# SCH_Survival-PC-3000_2026-08-28.net
KiCad netlist of a schematic drawn in EasyEDA
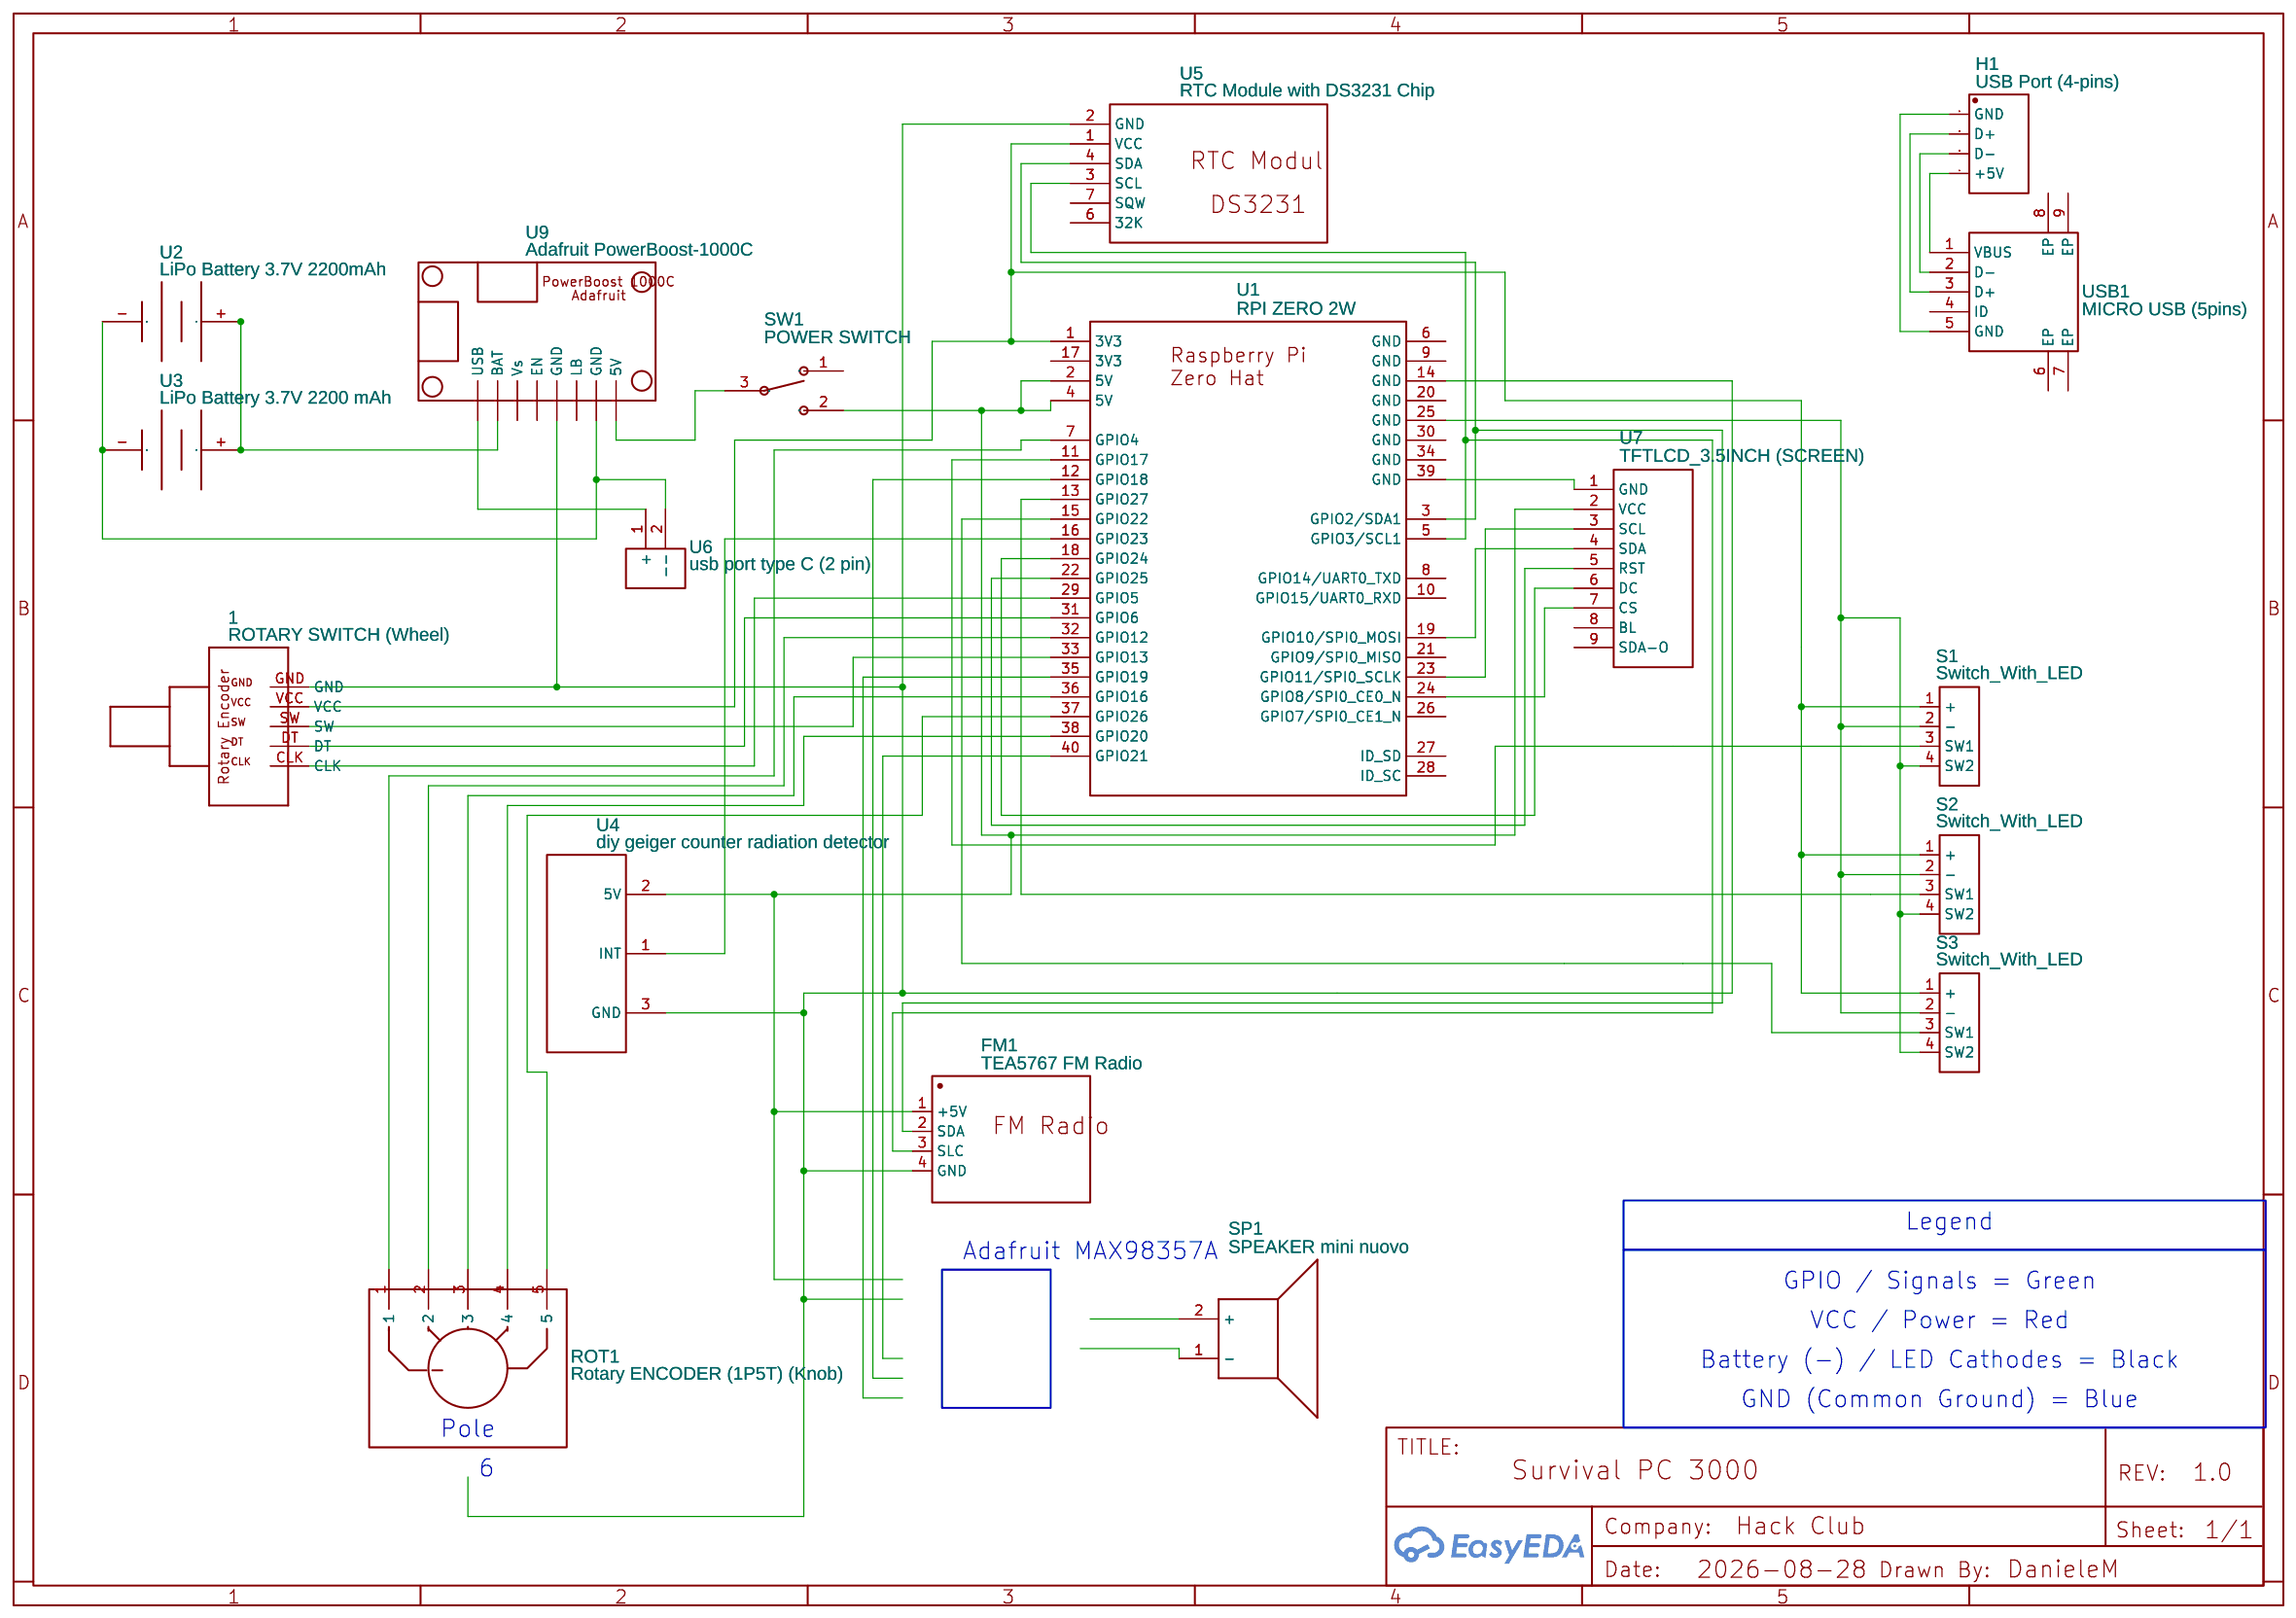
[diagram p0: schematic sheet]

(export (version "E")
  (design (tool "Eeschema 10.0.6"))
  (components
    (comp (ref "1") (value "ROTARY SWITCH (Wheel)") (libsource (lib "") (part "ROTARYENCODER")))
    (comp (ref "FM1")
      (value "TEA5767 FM Radio")
      (fields (field (name "Manufacturer Part") "Redon"))
      (libsource (lib "") (part "TEA5767 FM Radio"))
    )
    (comp (ref "H1")
      (value "USB Port (4-pins)")
      (fields
        (field (name "Manufacturer Part") "210S-1*4P L=11.6MMGold-plated black")
        (field (name "Manufacturer") "Ckmtw")
      )
      (libsource (lib "") (part "USB-Type-A-4-pins"))
    )
    (comp (ref "ROT1")
      (value "Rotary ENCODER (1P5T) (Knob)")
      (libsource (lib "") (part "Rotary RS1010 5 PIN"))
    )
    (comp (ref "S1") (value "Switch_With_LED") (libsource (lib "") (part "PB_Switch_With_LED")))
    (comp (ref "S2") (value "Switch_With_LED") (libsource (lib "") (part "PB_Switch_With_LED")))
    (comp (ref "S3") (value "Switch_With_LED") (libsource (lib "") (part "PB_Switch_With_LED")))
    (comp (ref "SP1") (value "SPEAKER mini nuovo") (libsource (lib "") (part "SPEAKER mini nuovo")))
    (comp (ref "SW1")
      (value "POWER SWITCH")
      (fields
        (field (name "Manufacturer Part") "450405020524")
        (field (name "Manufacturer") "Würth Elektronik")
      )
      (libsource (lib "") (part "SMT 8.7 X 3.0 MM MINI SLIDE SWITCH"))
    )
    (comp (ref "U1")
      (value "RPI ZERO 2W")
      (fields (field (name "Manufacturer") "Raspberry Pi Foundation"))
      (libsource (lib "") (part "RPI ZERO 2W"))
    )
    (comp (ref "U2")
      (value "LiPo Battery 3.7V 2200mAh")
      (libsource (lib "") (part "Tenergy Li-ion 18650 3.7V 2200mAh"))
    )
    (comp (ref "U3")
      (value "LiPo Battery 3.7V 2200 mAh")
      (libsource (lib "") (part "Tenergy Li-ion 18650 3.7V 2200mAh"))
    )
    (comp (ref "U4")
      (value "diy geiger counter radiation detector")
      (libsource (lib "") (part "diy geiger counter radiation detector"))
    )
    (comp (ref "U5")
      (value "RTC Module with DS3231 Chip")
      (libsource (lib "") (part "RTC Modul with DS3231 Chip"))
    )
    (comp (ref "U6") (value "usb port type C (2 pin)") (libsource (lib "") (part "usb type C 2 pin")))
    (comp (ref "U7")
      (value "TFTLCD_3.5INCH (SCREEN)")
      (libsource (lib "") (part "TFTLCD_3.5INCH_ST7796U_IO"))
    )
    (comp (ref "U9")
      (value "Adafruit PowerBoost-1000C")
      (libsource (lib "") (part "Adafruit PowerBoost-1000C"))
    )
    (comp (ref "USB1")
      (value "MICRO USB (5pins)")
      (fields (field (name "Manufacturer Part") "MicroUSB-5PIN"))
      (libsource (lib "") (part "MICROUSB-B-5PIN1"))
    )
  )
  (nets
    (net (code "1") (name "Net-(FM1-+5V)") (class "Default")
      (node (ref "FM1") (pin "1") (pinfunction "+5V_1") (pintype "unspecified"))
      (node (ref "SW1") (pin "2") (pinfunction "2_2") (pintype "unspecified"))
      (node (ref "U1") (pin "2") (pinfunction "5V_2") (pintype "unspecified"))
      (node (ref "U1") (pin "4") (pinfunction "5V_4") (pintype "unspecified"))
      (node (ref "U4") (pin "2") (pinfunction "5V_2") (pintype "unspecified"))
      (node (ref "U7") (pin "2") (pinfunction "VCC_2") (pintype "unspecified"))
    )
    (net (code "2") (name "Net-(FM1-GND)") (class "Default")
      (node (ref "FM1") (pin "4") (pinfunction "GND_4") (pintype "unspecified"))
      (node (ref "U1") (pin "14") (pinfunction "GND_14") (pintype "unspecified"))
      (node (ref "U4") (pin "3") (pinfunction "GND_3") (pintype "unspecified"))
      (node (ref "U5") (pin "2") (pinfunction "GND_2") (pintype "unspecified"))
      (node (ref "U9") (pin "5") (pinfunction "GND_5") (pintype "unspecified"))
    )
    (net (code "3") (name "Net-(FM1-SDA)") (class "Default")
      (node (ref "FM1") (pin "2") (pinfunction "SDA_2") (pintype "unspecified"))
      (node (ref "U1") (pin "3") (pinfunction "GPIO2/SDA1_3") (pintype "unspecified"))
      (node (ref "U5") (pin "4") (pinfunction "SDA_4") (pintype "unspecified"))
    )
    (net (code "4") (name "Net-(FM1-SLC)") (class "Default")
      (node (ref "FM1") (pin "3") (pinfunction "SLC_3") (pintype "unspecified"))
      (node (ref "U1") (pin "5") (pinfunction "GPIO3/SCL1_5") (pintype "unspecified"))
      (node (ref "U5") (pin "3") (pinfunction "SCL_3") (pintype "unspecified"))
    )
    (net (code "5") (name "Net-(H1-+5V)") (class "Default")
      (node (ref "H1") (pin "4") (pinfunction "+5V_4") (pintype "unspecified"))
      (node (ref "USB1") (pin "1") (pinfunction "VBUS_1") (pintype "unspecified"))
    )
    (net (code "6") (name "Net-(H1-D+)") (class "Default")
      (node (ref "H1") (pin "2") (pinfunction "D+_2") (pintype "unspecified"))
      (node (ref "USB1") (pin "3") (pinfunction "D+_3") (pintype "unspecified"))
    )
    (net (code "7") (name "Net-(H1-D-)") (class "Default")
      (node (ref "H1") (pin "3") (pinfunction "D-_3") (pintype "unspecified"))
      (node (ref "USB1") (pin "2") (pinfunction "D-_2") (pintype "unspecified"))
    )
    (net (code "8") (name "Net-(H1-GND)") (class "Default")
      (node (ref "H1") (pin "1") (pinfunction "GND_1") (pintype "unspecified"))
      (node (ref "USB1") (pin "5") (pinfunction "GND_5") (pintype "unspecified"))
    )
    (net (code "9") (name "Net-(S1-+)") (class "Default")
      (node (ref "S1") (pin "1") (pinfunction "+_1") (pintype "unspecified"))
      (node (ref "S2") (pin "1") (pinfunction "+_1") (pintype "unspecified"))
      (node (ref "S3") (pin "1") (pinfunction "+_1") (pintype "unspecified"))
      (node (ref "U1") (pin "1") (pinfunction "3V3_1") (pintype "unspecified"))
      (node (ref "U5") (pin "1") (pinfunction "VCC_1") (pintype "unspecified"))
    )
    (net (code "10") (name "Net-(S1--)") (class "Default")
      (node (ref "S1") (pin "2") (pinfunction "-_2") (pintype "unspecified"))
      (node (ref "S1") (pin "4") (pinfunction "SW2_4") (pintype "unspecified"))
      (node (ref "S2") (pin "2") (pinfunction "-_2") (pintype "unspecified"))
      (node (ref "S2") (pin "4") (pinfunction "SW2_4") (pintype "unspecified"))
      (node (ref "S3") (pin "2") (pinfunction "-_2") (pintype "unspecified"))
      (node (ref "S3") (pin "4") (pinfunction "SW2_4") (pintype "unspecified"))
      (node (ref "U1") (pin "25") (pinfunction "GND_25") (pintype "unspecified"))
    )
    (net (code "11") (name "Net-(S1-SW1)") (class "Default")
      (node (ref "S1") (pin "3") (pinfunction "SW1_3") (pintype "unspecified"))
      (node (ref "U1") (pin "11") (pinfunction "GPIO17_11") (pintype "unspecified"))
    )
    (net (code "12") (name "Net-(S2-SW1)") (class "Default")
      (node (ref "S2") (pin "3") (pinfunction "SW1_3") (pintype "unspecified"))
      (node (ref "U1") (pin "13") (pinfunction "GPIO27_13") (pintype "unspecified"))
    )
    (net (code "13") (name "Net-(S3-SW1)") (class "Default")
      (node (ref "S3") (pin "3") (pinfunction "SW1_3") (pintype "unspecified"))
      (node (ref "U1") (pin "15") (pinfunction "GPIO22_15") (pintype "unspecified"))
    )
    (net (code "14") (name "Net-(U1-GPIO4)") (class "Default")
      (node (ref "ROT1") (pin "1") (pinfunction "1_1") (pintype "unspecified"))
      (node (ref "U1") (pin "7") (pinfunction "GPIO4_7") (pintype "unspecified"))
    )
    (net (code "15") (name "Net-(U1-GPIO8{slash}SPI0_CE0_N)") (class "Default")
      (node (ref "U1") (pin "24") (pinfunction "GPIO8/SPI0_CE0_N_24") (pintype "unspecified"))
      (node (ref "U7") (pin "7") (pinfunction "CS_7") (pintype "unspecified"))
    )
    (net (code "16") (name "Net-(U1-GPIO10{slash}SPI0_MOSI)") (class "Default")
      (node (ref "U1") (pin "19") (pinfunction "GPIO10/SPI0_MOSI_19") (pintype "unspecified"))
      (node (ref "U7") (pin "4") (pinfunction "SDA_4") (pintype "unspecified"))
    )
    (net (code "17") (name "Net-(U1-GPIO11{slash}SPI0_SCLK)") (class "Default")
      (node (ref "U1") (pin "23") (pinfunction "GPIO11/SPI0_SCLK_23") (pintype "unspecified"))
      (node (ref "U7") (pin "3") (pinfunction "SCL_3") (pintype "unspecified"))
    )
    (net (code "18") (name "Net-(U1-GPIO12)") (class "Default")
      (node (ref "ROT1") (pin "2") (pinfunction "2_2") (pintype "unspecified"))
      (node (ref "U1") (pin "32") (pinfunction "GPIO12_32") (pintype "unspecified"))
    )
    (net (code "19") (name "Net-(U1-GPIO16)") (class "Default")
      (node (ref "ROT1") (pin "3") (pinfunction "3_3") (pintype "unspecified"))
      (node (ref "U1") (pin "36") (pinfunction "GPIO16_36") (pintype "unspecified"))
    )
    (net (code "20") (name "Net-(U1-GPIO20)") (class "Default")
      (node (ref "ROT1") (pin "4") (pinfunction "4_4") (pintype "unspecified"))
      (node (ref "U1") (pin "38") (pinfunction "GPIO20_38") (pintype "unspecified"))
    )
    (net (code "21") (name "Net-(U1-GPIO23)") (class "Default")
      (node (ref "U1") (pin "16") (pinfunction "GPIO23_16") (pintype "unspecified"))
      (node (ref "U4") (pin "1") (pinfunction "INT_1") (pintype "unspecified"))
    )
    (net (code "22") (name "Net-(U1-GPIO24)") (class "Default")
      (node (ref "U1") (pin "18") (pinfunction "GPIO24_18") (pintype "unspecified"))
      (node (ref "U7") (pin "6") (pinfunction "DC_6") (pintype "unspecified"))
    )
    (net (code "23") (name "Net-(U1-GPIO25)") (class "Default")
      (node (ref "U1") (pin "22") (pinfunction "GPIO25_22") (pintype "unspecified"))
      (node (ref "U7") (pin "5") (pinfunction "RST_5") (pintype "unspecified"))
    )
    (net (code "24") (name "Net-(U1-GPIO26)") (class "Default")
      (node (ref "ROT1") (pin "5") (pinfunction "5_5") (pintype "unspecified"))
      (node (ref "U1") (pin "37") (pinfunction "GPIO26_37") (pintype "unspecified"))
    )
    (net (code "25") (name "Net-(U2-1)") (class "Default")
      (node (ref "U2") (pin "+") (pinfunction "1_+") (pintype "unspecified"))
      (node (ref "U3") (pin "+") (pinfunction "1_+") (pintype "unspecified"))
      (node (ref "U9") (pin "2") (pinfunction "BAT_2") (pintype "unspecified"))
    )
    (net (code "26") (name "Net-(U2-2)") (class "Default")
      (node (ref "U2") (pin "-") (pinfunction "2_-") (pintype "unspecified"))
      (node (ref "U3") (pin "-") (pinfunction "2_-") (pintype "unspecified"))
      (node (ref "U6") (pin "2") (pinfunction "--_2") (pintype "unspecified"))
      (node (ref "U9") (pin "7") (pinfunction "GND_7") (pintype "unspecified"))
    )
    (net (code "27") (name "Net-(U6-+)") (class "Default")
      (node (ref "U6") (pin "1") (pinfunction "+_1") (pintype "unspecified"))
      (node (ref "U9") (pin "1") (pinfunction "USB_1") (pintype "unspecified"))
    )
    (net (code "28") (name "Net-(U7-GND)") (class "Default")
      (node (ref "U1") (pin "39") (pinfunction "GND_39") (pintype "unspecified"))
      (node (ref "U7") (pin "1") (pinfunction "GND_1") (pintype "unspecified"))
    )
    (net (code "29") (name "Net-(U9-5V)") (class "Default")
      (node (ref "SW1") (pin "3") (pinfunction "3_3") (pintype "unspecified"))
      (node (ref "U9") (pin "8") (pinfunction "5V_8") (pintype "unspecified"))
    )
    (net (code "30") (name "unconnected-(1-PadCLK)") (class "Default")
      (node (ref "1") (pin "CLK") (pinfunction "CLK_CLK") (pintype "bidirectional"))
    )
    (net (code "31") (name "unconnected-(1-PadDT)") (class "Default")
      (node (ref "1") (pin "DT") (pinfunction "DT_DT") (pintype "bidirectional"))
    )
    (net (code "32") (name "unconnected-(1-PadGND)") (class "Default")
      (node (ref "1") (pin "GND") (pinfunction "GND_GND") (pintype "bidirectional"))
    )
    (net (code "33") (name "unconnected-(1-PadSW)") (class "Default")
      (node (ref "1") (pin "SW") (pinfunction "SW_SW") (pintype "bidirectional"))
    )
    (net (code "34") (name "unconnected-(1-PadVCC)") (class "Default")
      (node (ref "1") (pin "VCC") (pinfunction "VCC_VCC") (pintype "bidirectional"))
    )
    (net (code "35") (name "unconnected-(SP1-+-Pad2)") (class "Default")
      (node (ref "SP1") (pin "2") (pinfunction "+_2") (pintype "unspecified"))
    )
    (net (code "36") (name "unconnected-(SP1---Pad1)") (class "Default")
      (node (ref "SP1") (pin "1") (pinfunction "-_1") (pintype "unspecified"))
    )
    (net (code "37") (name "unconnected-(SW1-Pad1)") (class "Default")
      (node (ref "SW1") (pin "1") (pinfunction "1_1") (pintype "unspecified"))
    )
    (net (code "38") (name "unconnected-(U1-3V3-Pad17)") (class "Default")
      (node (ref "U1") (pin "17") (pinfunction "3V3_17") (pintype "unspecified"))
    )
    (net (code "39") (name "unconnected-(U1-GND-Pad6)") (class "Default")
      (node (ref "U1") (pin "6") (pinfunction "GND_6") (pintype "unspecified"))
    )
    (net (code "40") (name "unconnected-(U1-GND-Pad9)") (class "Default")
      (node (ref "U1") (pin "9") (pinfunction "GND_9") (pintype "unspecified"))
    )
    (net (code "41") (name "unconnected-(U1-GND-Pad20)") (class "Default")
      (node (ref "U1") (pin "20") (pinfunction "GND_20") (pintype "unspecified"))
    )
    (net (code "42") (name "unconnected-(U1-GND-Pad30)") (class "Default")
      (node (ref "U1") (pin "30") (pinfunction "GND_30") (pintype "unspecified"))
    )
    (net (code "43") (name "unconnected-(U1-GND-Pad34)") (class "Default")
      (node (ref "U1") (pin "34") (pinfunction "GND_34") (pintype "unspecified"))
    )
    (net (code "44") (name "unconnected-(U1-GPIO5-Pad29)") (class "Default")
      (node (ref "U1") (pin "29") (pinfunction "GPIO5_29") (pintype "unspecified"))
    )
    (net (code "45") (name "unconnected-(U1-GPIO6-Pad31)") (class "Default")
      (node (ref "U1") (pin "31") (pinfunction "GPIO6_31") (pintype "unspecified"))
    )
    (net (code "46") (name "unconnected-(U1-GPIO7{slash}SPI0_CE1_N-Pad26)") (class "Default")
      (node (ref "U1") (pin "26") (pinfunction "GPIO7/SPI0_CE1_N_26") (pintype "unspecified"))
    )
    (net (code "47") (name "unconnected-(U1-GPIO9{slash}SPI0_MISO-Pad21)") (class "Default")
      (node (ref "U1") (pin "21") (pinfunction "GPIO9/SPI0_MISO_21") (pintype "unspecified"))
    )
    (net (code "48") (name "unconnected-(U1-GPIO13-Pad33)") (class "Default")
      (node (ref "U1") (pin "33") (pinfunction "GPIO13_33") (pintype "unspecified"))
    )
    (net (code "49") (name "unconnected-(U1-GPIO14{slash}UART0_TXD-Pad8)") (class "Default")
      (node (ref "U1") (pin "8") (pinfunction "GPIO14/UART0_TXD_8") (pintype "unspecified"))
    )
    (net (code "50") (name "unconnected-(U1-GPIO15{slash}UART0_RXD-Pad10)") (class "Default")
      (node (ref "U1") (pin "10") (pinfunction "GPIO15/UART0_RXD_10") (pintype "unspecified"))
    )
    (net (code "51") (name "unconnected-(U1-GPIO18-Pad12)") (class "Default")
      (node (ref "U1") (pin "12") (pinfunction "GPIO18_12") (pintype "unspecified"))
    )
    (net (code "52") (name "unconnected-(U1-GPIO19-Pad35)") (class "Default")
      (node (ref "U1") (pin "35") (pinfunction "GPIO19_35") (pintype "unspecified"))
    )
    (net (code "53") (name "unconnected-(U1-GPIO21-Pad40)") (class "Default")
      (node (ref "U1") (pin "40") (pinfunction "GPIO21_40") (pintype "unspecified"))
    )
    (net (code "54") (name "unconnected-(U1-ID_SC-Pad28)") (class "Default")
      (node (ref "U1") (pin "28") (pinfunction "ID_SC_28") (pintype "unspecified"))
    )
    (net (code "55") (name "unconnected-(U1-ID_SD-Pad27)") (class "Default")
      (node (ref "U1") (pin "27") (pinfunction "ID_SD_27") (pintype "unspecified"))
    )
    (net (code "56") (name "unconnected-(U5-32K-Pad6)") (class "Default")
      (node (ref "U5") (pin "6") (pinfunction "32K_6") (pintype "unspecified"))
    )
    (net (code "57") (name "unconnected-(U5-SQW-Pad7)") (class "Default")
      (node (ref "U5") (pin "7") (pinfunction "SQW_7") (pintype "unspecified"))
    )
    (net (code "58") (name "unconnected-(U7-BL-Pad8)") (class "Default")
      (node (ref "U7") (pin "8") (pinfunction "BL_8") (pintype "unspecified"))
    )
    (net (code "59") (name "unconnected-(U7-SDA-O-Pad9)") (class "Default")
      (node (ref "U7") (pin "9") (pinfunction "SDA-O_9") (pintype "unspecified"))
    )
    (net (code "60") (name "unconnected-(U9-EN-Pad4)") (class "Default")
      (node (ref "U9") (pin "4") (pinfunction "EN_4") (pintype "unspecified"))
    )
    (net (code "61") (name "unconnected-(U9-LB-Pad6)") (class "Default")
      (node (ref "U9") (pin "6") (pinfunction "LB_6") (pintype "unspecified"))
    )
    (net (code "62") (name "unconnected-(U9-Vs-Pad3)") (class "Default")
      (node (ref "U9") (pin "3") (pinfunction "Vs_3") (pintype "unspecified"))
    )
    (net (code "63") (name "unconnected-(USB1-EP-Pad6)") (class "Default")
      (node (ref "USB1") (pin "6") (pinfunction "EP_6") (pintype "unspecified"))
    )
    (net (code "64") (name "unconnected-(USB1-EP-Pad7)") (class "Default")
      (node (ref "USB1") (pin "7") (pinfunction "EP_7") (pintype "unspecified"))
    )
    (net (code "65") (name "unconnected-(USB1-EP-Pad8)") (class "Default")
      (node (ref "USB1") (pin "8") (pinfunction "EP_8") (pintype "unspecified"))
    )
    (net (code "66") (name "unconnected-(USB1-EP-Pad9)") (class "Default")
      (node (ref "USB1") (pin "9") (pinfunction "EP_9") (pintype "unspecified"))
    )
    (net (code "67") (name "unconnected-(USB1-ID-Pad4)") (class "Default")
      (node (ref "USB1") (pin "4") (pinfunction "ID_4") (pintype "unspecified"))
    )
  )
)
